# ProPrj_FireWheels_2025-05-02.net
KiCad netlist of a schematic drawn in EasyEDA Pro
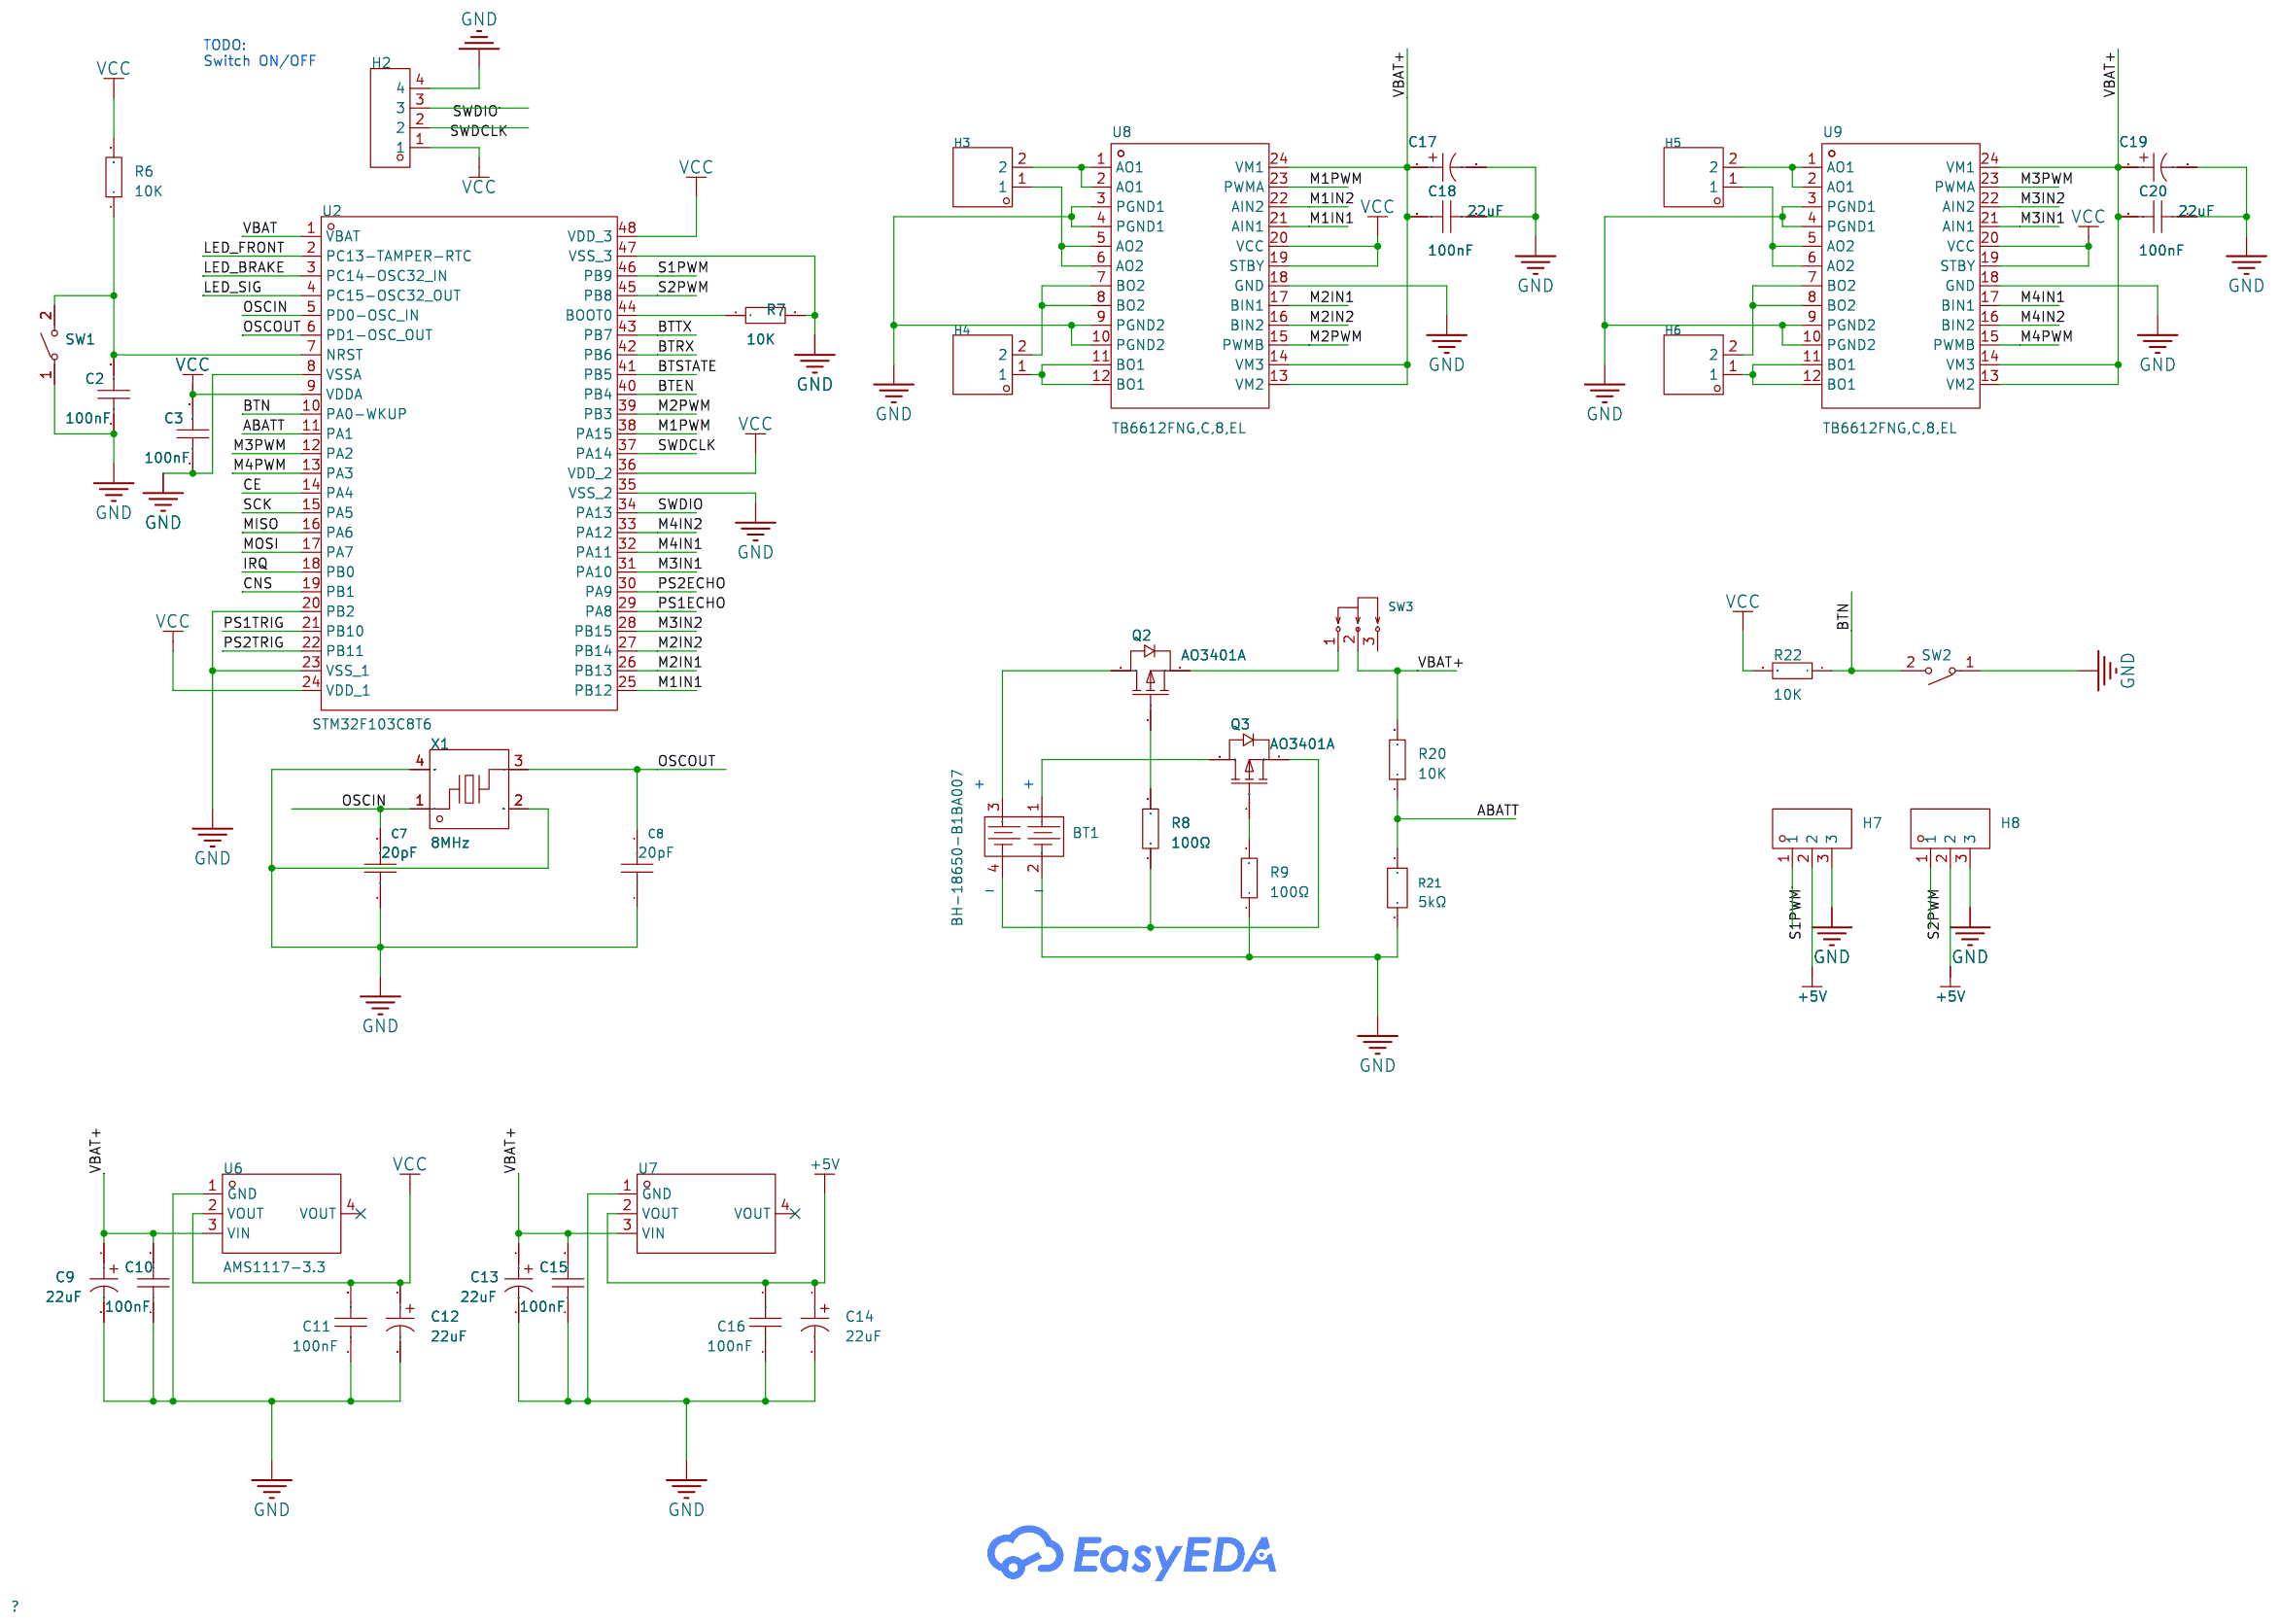
[diagram p0: P1]
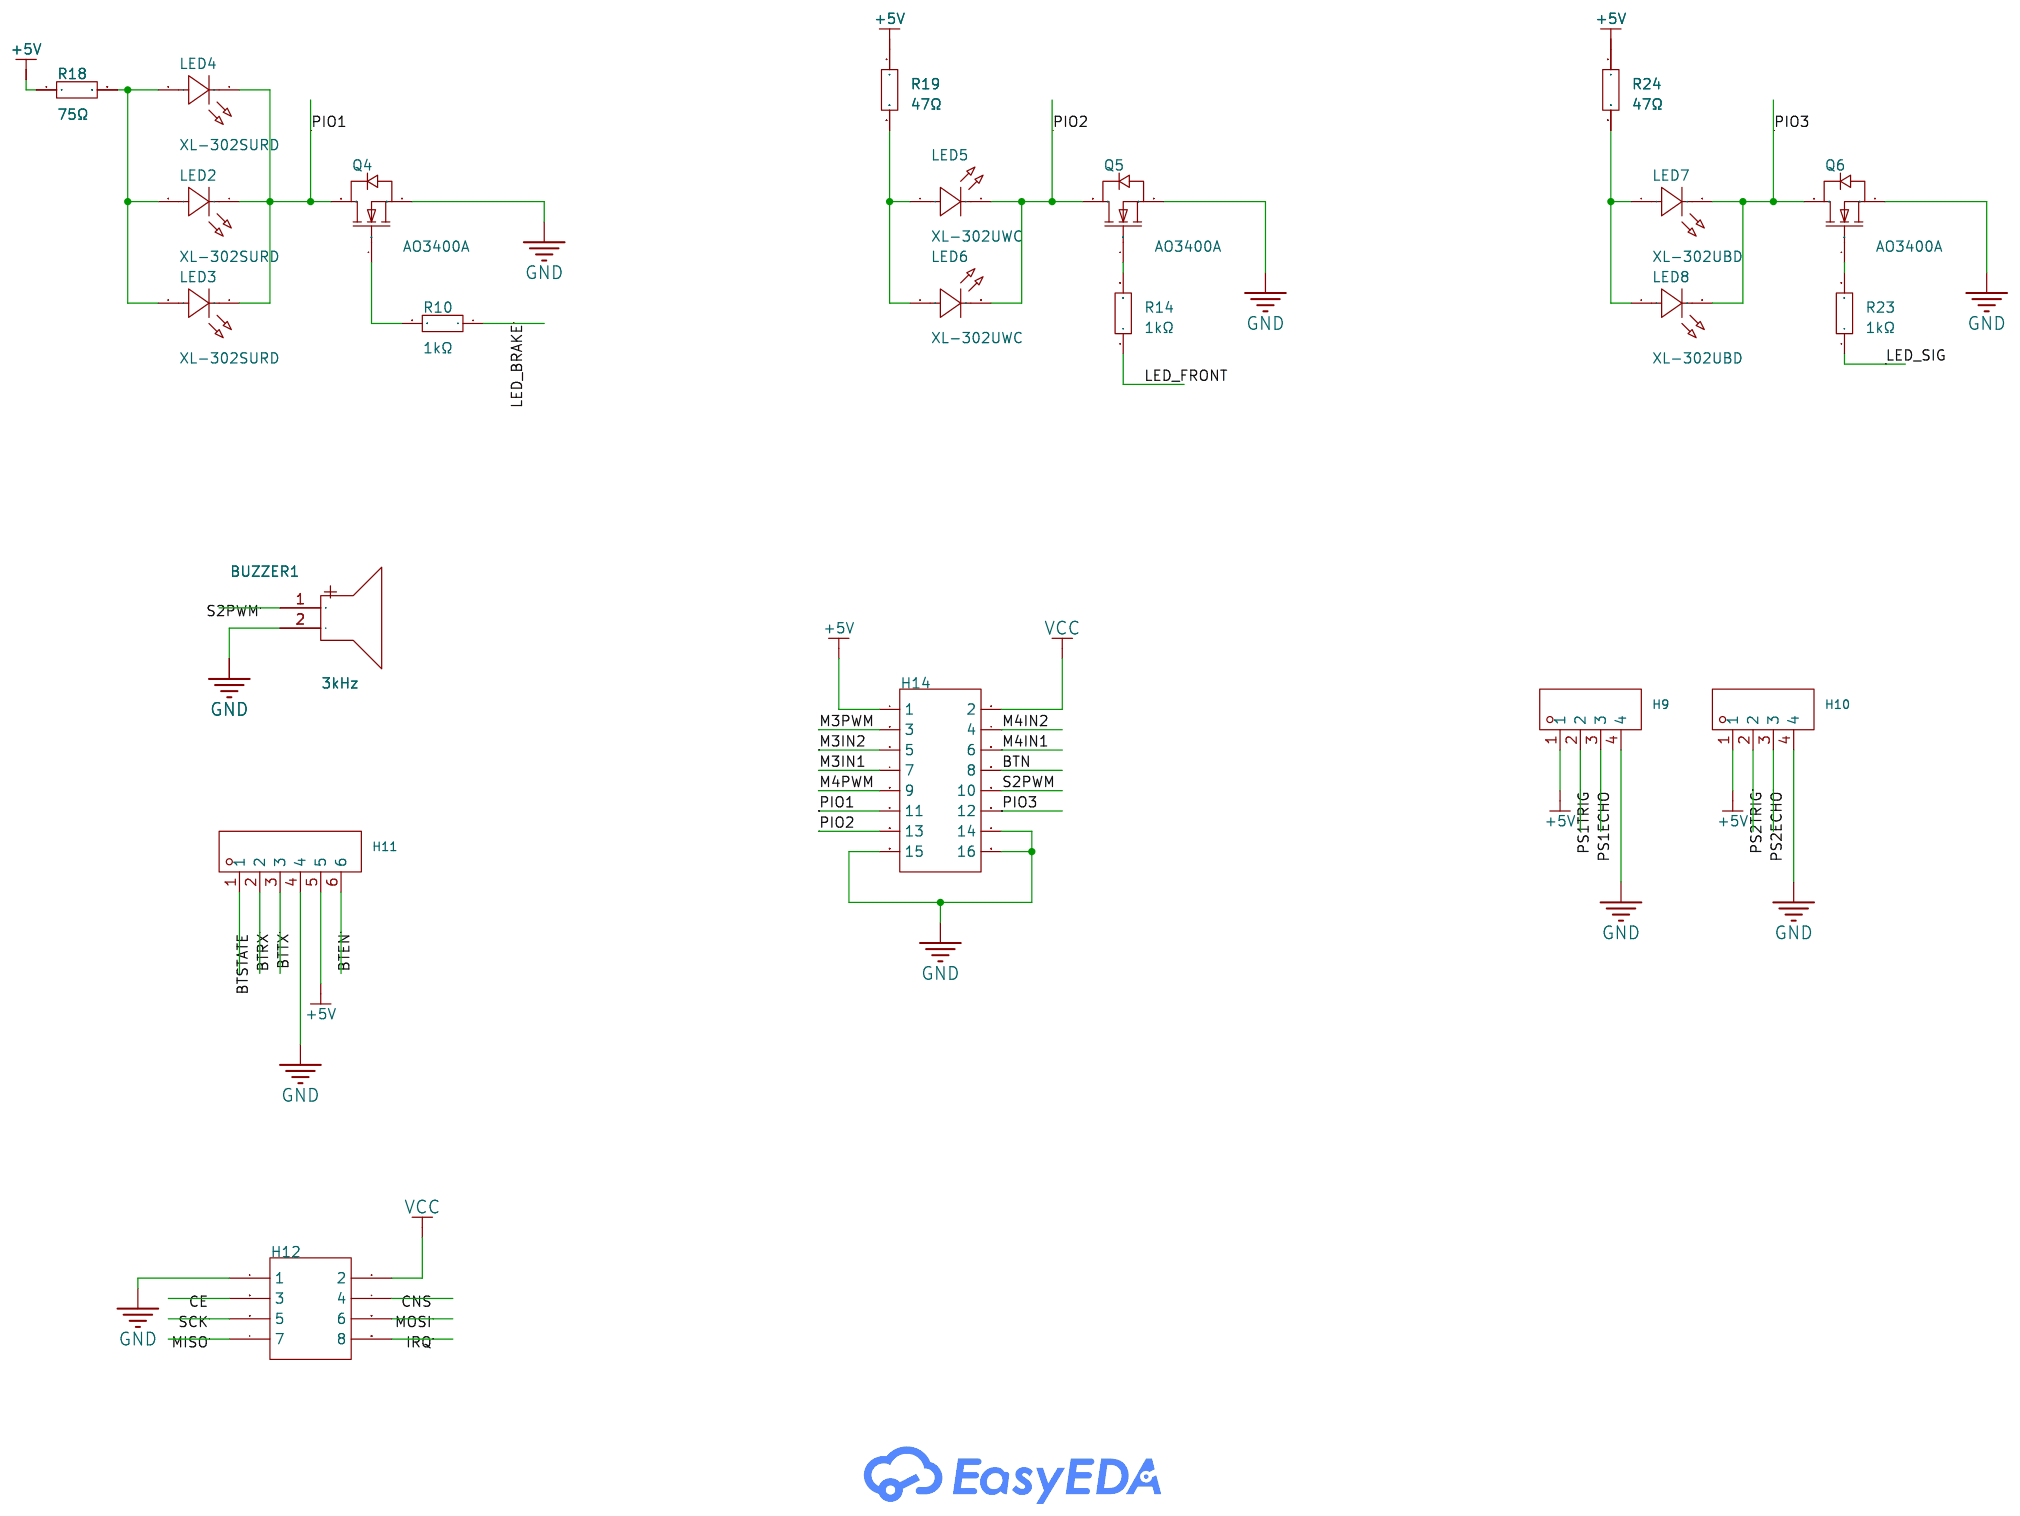
[diagram p1: P2]

(export (version "E")
  (design (tool "Eeschema 10.0.6"))
  (components
    (comp (ref "BT1")
      (value "BH-18650-B1BA007")
      (footprint "easyedapro:BAT-SMD_BH-18650-B1BA007")
      (fields (field (name "Manufacturer") "MYOUNG(美阳)"))
      (libsource (lib "easyedapro") (part "BH-18650-B1BA007"))
    )
    (comp (ref "C2")
      (value "100nF")
      (footprint "easyedapro:C0805")
      (fields (field (name "Manufacturer Part") "0805B104K250NT") (field (name "Manufacturer") "FH(风华)"))
      (libsource (lib "easyedapro") (part "0805B104K250NT"))
    )
    (comp (ref "C3")
      (value "100nF")
      (footprint "easyedapro:C0805")
      (fields (field (name "Manufacturer Part") "0805B104K250NT") (field (name "Manufacturer") "FH(风华)"))
      (libsource (lib "easyedapro") (part "0805B104K250NT"))
    )
    (comp (ref "C7")
      (value "20pF")
      (footprint "easyedapro:C0603")
      (fields
        (field (name "Manufacturer Part") "TCC0603COG200J500CT")
        (field (name "Manufacturer") "CCTC(三环)")
      )
      (libsource (lib "easyedapro") (part "TCC0603COG200J500CT"))
    )
    (comp (ref "C8")
      (value "20pF")
      (footprint "easyedapro:C0603")
      (fields
        (field (name "Manufacturer Part") "TCC0603COG200J500CT")
        (field (name "Manufacturer") "CCTC(三环)")
      )
      (libsource (lib "easyedapro") (part "TCC0603COG200J500CT"))
    )
    (comp (ref "C9")
      (value "22uF")
      (footprint "easyedapro:CAP-SMD_L3.5-W2.8-FD")
      (fields (field (name "Manufacturer Part") "T491B226K004AT") (field (name "Manufacturer") "KEMET(基美)"))
      (libsource (lib "easyedapro") (part "T491B226K004AT"))
    )
    (comp (ref "C10")
      (value "100nF")
      (footprint "easyedapro:C0805")
      (fields (field (name "Manufacturer Part") "0805B104K250NT") (field (name "Manufacturer") "FH(风华)"))
      (libsource (lib "easyedapro") (part "0805B104K250NT"))
    )
    (comp (ref "C11")
      (value "100nF")
      (footprint "easyedapro:C0805")
      (fields (field (name "Manufacturer Part") "0805B104K250NT") (field (name "Manufacturer") "FH(风华)"))
      (libsource (lib "easyedapro") (part "0805B104K250NT"))
    )
    (comp (ref "C12")
      (value "22uF")
      (footprint "easyedapro:CAP-SMD_L3.5-W2.8-FD")
      (fields (field (name "Manufacturer Part") "T491B226K004AT") (field (name "Manufacturer") "KEMET(基美)"))
      (libsource (lib "easyedapro") (part "T491B226K004AT"))
    )
    (comp (ref "C13")
      (value "22uF")
      (footprint "easyedapro:CAP-SMD_L3.5-W2.8-FD")
      (fields (field (name "Manufacturer Part") "T491B226K004AT") (field (name "Manufacturer") "KEMET(基美)"))
      (libsource (lib "easyedapro") (part "T491B226K004AT"))
    )
    (comp (ref "C14")
      (value "22uF")
      (footprint "easyedapro:CAP-SMD_L3.5-W2.8-FD")
      (fields (field (name "Manufacturer Part") "T491B226K004AT") (field (name "Manufacturer") "KEMET(基美)"))
      (libsource (lib "easyedapro") (part "T491B226K004AT"))
    )
    (comp (ref "C15")
      (value "100nF")
      (footprint "easyedapro:C0805")
      (fields (field (name "Manufacturer Part") "0805B104K250NT") (field (name "Manufacturer") "FH(风华)"))
      (libsource (lib "easyedapro") (part "0805B104K250NT"))
    )
    (comp (ref "C16")
      (value "100nF")
      (footprint "easyedapro:C0805")
      (fields (field (name "Manufacturer Part") "0805B104K250NT") (field (name "Manufacturer") "FH(风华)"))
      (libsource (lib "easyedapro") (part "0805B104K250NT"))
    )
    (comp (ref "C17")
      (value "22uF")
      (footprint "easyedapro:CAP-SMD_L3.5-W2.8-FD")
      (fields (field (name "Manufacturer Part") "T491B226K004AT") (field (name "Manufacturer") "KEMET(基美)"))
      (libsource (lib "easyedapro") (part "T491B226K004AT"))
    )
    (comp (ref "C18")
      (value "100nF")
      (footprint "easyedapro:C0805")
      (fields (field (name "Manufacturer Part") "0805B104K250NT") (field (name "Manufacturer") "FH(风华)"))
      (libsource (lib "easyedapro") (part "0805B104K250NT"))
    )
    (comp (ref "C19")
      (value "22uF")
      (footprint "easyedapro:CAP-SMD_L3.5-W2.8-FD")
      (fields (field (name "Manufacturer Part") "T491B226K004AT") (field (name "Manufacturer") "KEMET(基美)"))
      (libsource (lib "easyedapro") (part "T491B226K004AT"))
    )
    (comp (ref "C20")
      (value "100nF")
      (footprint "easyedapro:C0805")
      (fields (field (name "Manufacturer Part") "0805B104K250NT") (field (name "Manufacturer") "FH(风华)"))
      (libsource (lib "easyedapro") (part "0805B104K250NT"))
    )
    (comp (ref "H2")
      (value "~")
      (footprint "easyedapro:HDR-TH_4P-P2.54-V-M")
      (libsource (lib "easyedapro") (part "PZ254V-11-04P"))
    )
    (comp (ref "H3")
      (value "~")
      (footprint "easyedapro:HDR-TH_2P-P2.54-V-M-1")
      (libsource (lib "easyedapro") (part "210S-1*2P L=11.6MMGold-plated black"))
    )
    (comp (ref "H4")
      (value "~")
      (footprint "easyedapro:HDR-TH_2P-P2.54-V-M-1")
      (libsource (lib "easyedapro") (part "210S-1*2P L=11.6MMGold-plated black"))
    )
    (comp (ref "H5")
      (value "~")
      (footprint "easyedapro:HDR-TH_2P-P2.54-V-M-1")
      (libsource (lib "easyedapro") (part "210S-1*2P L=11.6MMGold-plated black"))
    )
    (comp (ref "H6")
      (value "~")
      (footprint "easyedapro:HDR-TH_2P-P2.54-V-M-1")
      (libsource (lib "easyedapro") (part "210S-1*2P L=11.6MMGold-plated black"))
    )
    (comp (ref "H7")
      (value "~")
      (footprint "easyedapro:HDR-TH_3P-P2.54-V-M")
      (libsource (lib "easyedapro") (part "PZ254V-11-03P_C2937625"))
    )
    (comp (ref "H8")
      (value "~")
      (footprint "easyedapro:HDR-TH_3P-P2.54-V-M")
      (libsource (lib "easyedapro") (part "PZ254V-11-03P_C2937625"))
    )
    (comp (ref "Q2")
      (value "AO3401A")
      (footprint "easyedapro:SOT-23_L2.9-W1.3-P1.90-LS2.4-BR")
      (fields (field (name "Manufacturer") "AOS"))
      (libsource (lib "easyedapro") (part "AO3401A"))
    )
    (comp (ref "Q3")
      (value "AO3401A")
      (footprint "easyedapro:SOT-23_L2.9-W1.3-P1.90-LS2.4-BR")
      (fields (field (name "Manufacturer") "AOS"))
      (libsource (lib "easyedapro") (part "AO3401A"))
    )
    (comp (ref "R6") (value "10K") (footprint "easyedapro:R0603") (libsource (lib "easyedapro") (part "Res")))
    (comp (ref "R7") (value "10K") (footprint "easyedapro:R0603") (libsource (lib "easyedapro") (part "Res")))
    (comp (ref "R8")
      (value "100Ω")
      (footprint "easyedapro:R0603")
      (fields
        (field (name "Manufacturer Part") "0603WAF1000T5E")
        (field (name "Manufacturer") "UNI-ROYAL(厚声)")
      )
      (libsource (lib "easyedapro") (part "0603WAF1000T5E"))
    )
    (comp (ref "R9")
      (value "100Ω")
      (footprint "easyedapro:R0603")
      (fields
        (field (name "Manufacturer Part") "0603WAF1000T5E")
        (field (name "Manufacturer") "UNI-ROYAL(厚声)")
      )
      (libsource (lib "easyedapro") (part "0603WAF1000T5E"))
    )
    (comp (ref "R20")
      (value "10K")
      (footprint "easyedapro:R0603")
      (libsource (lib "easyedapro") (part "Res"))
    )
    (comp (ref "R21")
      (value "5kΩ")
      (footprint "easyedapro:R0603")
      (fields (field (name "Manufacturer Part") "RTT035001FTP") (field (name "Manufacturer") "RALEC(旺诠)"))
      (libsource (lib "easyedapro") (part "RTT035001FTP"))
    )
    (comp (ref "R22")
      (value "10K")
      (footprint "easyedapro:R0603")
      (libsource (lib "easyedapro") (part "Res"))
    )
    (comp (ref "SW1")
      (value "~")
      (footprint "easyedapro:SW-SMD_L3.9-W3.0-P4.45")
      (fields (field (name "Manufacturer Part") "TS-1088R-02026") (field (name "Manufacturer") "XUNPU(讯普)"))
      (libsource (lib "easyedapro") (part "TS-1088R-02026"))
    )
    (comp (ref "SW2")
      (value "~")
      (footprint "easyedapro:SW-SMD_L3.9-W3.0-P4.45")
      (fields (field (name "Manufacturer Part") "TS-1088R-02026") (field (name "Manufacturer") "XUNPU(讯普)"))
      (libsource (lib "easyedapro") (part "TS-1088R-02026"))
    )
    (comp (ref "SW3")
      (value "SS12D10G4 071")
      (footprint "easyedapro:SW-TH_SHOU-HAN_SS12D10G4")
      (fields (field (name "Manufacturer") "SHOU HAN(首韩)"))
      (libsource (lib "easyedapro") (part "SS12D10G4 071"))
    )
    (comp (ref "U2")
      (value "STM32F103C8T6")
      (footprint "easyedapro:LQFP-48_L7.0-W7.0-P0.50-LS9.0-BL")
      (fields (field (name "Manufacturer") "ST(意法半导体)"))
      (libsource (lib "easyedapro") (part "STM32F103C8T6"))
    )
    (comp (ref "U6")
      (value "AMS1117-3.3")
      (footprint "easyedapro:SOT-223-3_L6.7-W3.7-P2.30-LS7.0-BR")
      (fields (field (name "Manufacturer") "JSMSEMI(杰盛微)"))
      (libsource (lib "easyedapro") (part "AMS1117-3.3_C917183"))
    )
    (comp (ref "U7")
      (value "~")
      (footprint "easyedapro:SOT-223_L6.5-W3.5-P2.30-LS7.0-BR")
      (fields (field (name "Manufacturer Part") "AMS1117-5.0") (field (name "Manufacturer") "美国AMS"))
      (libsource (lib "easyedapro") (part "AMS1117-5.0"))
    )
    (comp (ref "U8")
      (value "TB6612FNG,C,8,EL")
      (footprint "easyedapro:SSOP-24_L8.3-W5.6-P0.65-LS7.6-BL")
      (fields (field (name "Manufacturer") "TOSHIBA(东芝)"))
      (libsource (lib "easyedapro") (part "TB6612FNG,C,8,EL"))
    )
    (comp (ref "U9")
      (value "TB6612FNG,C,8,EL")
      (footprint "easyedapro:SSOP-24_L8.3-W5.6-P0.65-LS7.6-BL")
      (fields (field (name "Manufacturer") "TOSHIBA(东芝)"))
      (libsource (lib "easyedapro") (part "TB6612FNG,C,8,EL"))
    )
    (comp (ref "X1")
      (value "8MHz")
      (footprint "easyedapro:CRYSTAL-SMD_4P-L3.2-W2.5-BL")
      (fields (field (name "Manufacturer Part") "3TJ480000NWLAC") (field (name "Manufacturer") "JYJE(晶友嘉)"))
      (libsource (lib "easyedapro") (part "3TJ480000NWLAC"))
    )
    (comp (ref "BUZZER1")
      (value "3kHz")
      (footprint "easyedapro:BUZ-TH_BD9.0-P5.00-D0.6-FD")
      (fields (field (name "Manufacturer Part") "HNB09A03") (field (name "Manufacturer") "华能"))
      (libsource (lib "easyedapro") (part "HNB09A03"))
    )
    (comp (ref "H9")
      (value "~")
      (footprint "easyedapro:HDR-TH_4P-P2.54-V-F")
      (libsource (lib "easyedapro") (part "2.54-1*4P母"))
    )
    (comp (ref "H10")
      (value "~")
      (footprint "easyedapro:HDR-TH_4P-P2.54-V-F")
      (libsource (lib "easyedapro") (part "2.54-1*4P母"))
    )
    (comp (ref "H11")
      (value "~")
      (footprint "easyedapro:HDR-TH_6P-P2.54-V-F")
      (libsource (lib "easyedapro") (part "Header-Female-2.54_1x6"))
    )
    (comp (ref "H12")
      (value "~")
      (footprint "easyedapro:HDR-TH_8P-P2.54-V-F-R2-C4-S2.54-1")
      (libsource (lib "easyedapro") (part "HDR-F-2.54_2x4"))
    )
    (comp (ref "H14")
      (value "~")
      (footprint "easyedapro:HDR-TH_16P-P2.54-V-M-R2-C8-S2.54")
      (libsource (lib "easyedapro") (part "HDR-M-2.54_2x8"))
    )
    (comp (ref "LED2")
      (value "XL-302SURD")
      (footprint "easyedapro:LED-TH_BD3.8-P2.54-RD")
      (fields (field (name "Manufacturer") "XINGLIGHT(成兴光)"))
      (libsource (lib "easyedapro") (part "XL-302SURD"))
    )
    (comp (ref "LED3")
      (value "XL-302SURD")
      (footprint "easyedapro:LED-TH_BD3.8-P2.54-RD")
      (fields (field (name "Manufacturer") "XINGLIGHT(成兴光)"))
      (libsource (lib "easyedapro") (part "XL-302SURD"))
    )
    (comp (ref "LED4")
      (value "XL-302SURD")
      (footprint "easyedapro:LED-TH_BD3.8-P2.54-RD")
      (fields (field (name "Manufacturer") "XINGLIGHT(成兴光)"))
      (libsource (lib "easyedapro") (part "XL-302SURD"))
    )
    (comp (ref "LED5")
      (value "XL-302UWC")
      (footprint "easyedapro:LED-TH_BD3.8-P2.54-FD_WHITE")
      (fields (field (name "Manufacturer") "XINGLIGHT(成兴光)"))
      (libsource (lib "easyedapro") (part "XL-302UWC"))
    )
    (comp (ref "LED6")
      (value "XL-302UWC")
      (footprint "easyedapro:LED-TH_BD3.8-P2.54-FD_WHITE")
      (fields (field (name "Manufacturer") "XINGLIGHT(成兴光)"))
      (libsource (lib "easyedapro") (part "XL-302UWC"))
    )
    (comp (ref "LED7")
      (value "XL-302UBD")
      (footprint "easyedapro:LED-TH_BD3.8-P2.54-FD_BLUE")
      (fields (field (name "Manufacturer") "XINGLIGHT(成兴光)"))
      (libsource (lib "easyedapro") (part "XL-302UBD"))
    )
    (comp (ref "LED8")
      (value "XL-302UBD")
      (footprint "easyedapro:LED-TH_BD3.8-P2.54-FD_BLUE")
      (fields (field (name "Manufacturer") "XINGLIGHT(成兴光)"))
      (libsource (lib "easyedapro") (part "XL-302UBD"))
    )
    (comp (ref "Q4")
      (value "AO3400A")
      (footprint "easyedapro:SOT-23-3_L2.9-W1.3-P1.90-LS2.4-BR")
      (fields (field (name "Manufacturer") "AOS"))
      (libsource (lib "easyedapro") (part "AO3400A"))
    )
    (comp (ref "Q5")
      (value "AO3400A")
      (footprint "easyedapro:SOT-23-3_L2.9-W1.3-P1.90-LS2.4-BR")
      (fields (field (name "Manufacturer") "AOS"))
      (libsource (lib "easyedapro") (part "AO3400A"))
    )
    (comp (ref "Q6")
      (value "AO3400A")
      (footprint "easyedapro:SOT-23-3_L2.9-W1.3-P1.90-LS2.4-BR")
      (fields (field (name "Manufacturer") "AOS"))
      (libsource (lib "easyedapro") (part "AO3400A"))
    )
    (comp (ref "R10")
      (value "1kΩ")
      (footprint "easyedapro:R0603")
      (fields (field (name "Manufacturer Part") "RC0603FR-071KL") (field (name "Manufacturer") "YAGEO(国巨)"))
      (libsource (lib "easyedapro") (part "RC0603FR-071KL"))
    )
    (comp (ref "R14")
      (value "1kΩ")
      (footprint "easyedapro:R0603")
      (fields (field (name "Manufacturer Part") "RC0603FR-071KL") (field (name "Manufacturer") "YAGEO(国巨)"))
      (libsource (lib "easyedapro") (part "RC0603FR-071KL"))
    )
    (comp (ref "R18")
      (value "75Ω")
      (footprint "easyedapro:R1206")
      (fields (field (name "Manufacturer Part") "RC1206FR-0775RL") (field (name "Manufacturer") "YAGEO(国巨)"))
      (libsource (lib "easyedapro") (part "RC1206FR-0775RL"))
    )
    (comp (ref "R19")
      (value "47Ω")
      (footprint "easyedapro:R1206")
      (fields (field (name "Manufacturer Part") "RC1206FR-0747RL") (field (name "Manufacturer") "YAGEO(国巨)"))
      (libsource (lib "easyedapro") (part "RC1206FR-0747RL"))
    )
    (comp (ref "R23")
      (value "1kΩ")
      (footprint "easyedapro:R0603")
      (fields (field (name "Manufacturer Part") "RC0603FR-071KL") (field (name "Manufacturer") "YAGEO(国巨)"))
      (libsource (lib "easyedapro") (part "RC0603FR-071KL"))
    )
    (comp (ref "R24")
      (value "47Ω")
      (footprint "easyedapro:R1206")
      (fields (field (name "Manufacturer Part") "RC1206FR-0747RL") (field (name "Manufacturer") "YAGEO(国巨)"))
      (libsource (lib "easyedapro") (part "RC1206FR-0747RL"))
    )
  )
  (nets
    (net (code "1") (name "+5V") (class "Default")
      (node (ref "C14") (pin "1") (pinfunction "1_1") (pintype "input"))
      (node (ref "C16") (pin "2") (pinfunction "2_2") (pintype "unspecified"))
      (node (ref "H10") (pin "1") (pinfunction "1_1") (pintype "input"))
      (node (ref "H11") (pin "5") (pinfunction "5_5") (pintype "input"))
      (node (ref "H14") (pin "1") (pinfunction "1_1") (pintype "input"))
      (node (ref "H7") (pin "2") (pinfunction "2_2") (pintype "unspecified"))
      (node (ref "H8") (pin "2") (pinfunction "2_2") (pintype "unspecified"))
      (node (ref "H9") (pin "1") (pinfunction "1_1") (pintype "input"))
      (node (ref "R18") (pin "1") (pinfunction "1_1") (pintype "input"))
      (node (ref "R19") (pin "1") (pinfunction "1_1") (pintype "input"))
      (node (ref "R24") (pin "1") (pinfunction "1_1") (pintype "input"))
      (node (ref "U7") (pin "2") (pinfunction "VOUT_2") (pintype "input"))
    )
    (net (code "2") (name "ABATT") (class "Default")
      (node (ref "R20") (pin "1") (pinfunction "1_1") (pintype "input"))
      (node (ref "R21") (pin "2") (pinfunction "2_2") (pintype "input"))
      (node (ref "U2") (pin "11") (pinfunction "PA1_11") (pintype "unspecified"))
    )
    (net (code "3") (name "BTEN") (class "Default")
      (node (ref "H11") (pin "6") (pinfunction "6_6") (pintype "input"))
      (node (ref "U2") (pin "40") (pinfunction "PB4_40") (pintype "unspecified"))
    )
    (net (code "4") (name "BTN") (class "Default")
      (node (ref "H14") (pin "8") (pinfunction "8_8") (pintype "input"))
      (node (ref "R22") (pin "1") (pinfunction "1_1") (pintype "input"))
      (node (ref "SW2") (pin "2") (pinfunction "2_2") (pintype "input"))
      (node (ref "U2") (pin "10") (pinfunction "PA0-WKUP_10") (pintype "unspecified"))
    )
    (net (code "5") (name "BTRX") (class "Default")
      (node (ref "H11") (pin "2") (pinfunction "2_2") (pintype "input"))
      (node (ref "U2") (pin "42") (pinfunction "PB6_42") (pintype "unspecified"))
    )
    (net (code "6") (name "BTSTATE") (class "Default")
      (node (ref "H11") (pin "1") (pinfunction "1_1") (pintype "input"))
      (node (ref "U2") (pin "41") (pinfunction "PB5_41") (pintype "unspecified"))
    )
    (net (code "7") (name "BTTX") (class "Default")
      (node (ref "H11") (pin "3") (pinfunction "3_3") (pintype "input"))
      (node (ref "U2") (pin "43") (pinfunction "PB7_43") (pintype "unspecified"))
    )
    (net (code "8") (name "CE") (class "Default")
      (node (ref "H12") (pin "3") (pinfunction "3_3") (pintype "input"))
      (node (ref "U2") (pin "14") (pinfunction "PA4_14") (pintype "unspecified"))
    )
    (net (code "9") (name "CNS") (class "Default")
      (node (ref "H12") (pin "4") (pinfunction "4_4") (pintype "input"))
      (node (ref "U2") (pin "19") (pinfunction "PB1_19") (pintype "unspecified"))
    )
    (net (code "10") (name "GND") (class "Default")
      (node (ref "BT1") (pin "2") (pinfunction "2_2") (pintype "input"))
      (node (ref "BUZZER1") (pin "2") (pinfunction "-_2") (pintype "unspecified"))
      (node (ref "C10") (pin "1") (pinfunction "1_1") (pintype "unspecified"))
      (node (ref "C11") (pin "1") (pinfunction "1_1") (pintype "unspecified"))
      (node (ref "C12") (pin "2") (pinfunction "2_2") (pintype "input"))
      (node (ref "C13") (pin "2") (pinfunction "2_2") (pintype "input"))
      (node (ref "C14") (pin "2") (pinfunction "2_2") (pintype "input"))
      (node (ref "C15") (pin "1") (pinfunction "1_1") (pintype "unspecified"))
      (node (ref "C16") (pin "1") (pinfunction "1_1") (pintype "unspecified"))
      (node (ref "C17") (pin "2") (pinfunction "2_2") (pintype "input"))
      (node (ref "C18") (pin "1") (pinfunction "1_1") (pintype "unspecified"))
      (node (ref "C19") (pin "2") (pinfunction "2_2") (pintype "input"))
      (node (ref "C2") (pin "1") (pinfunction "1_1") (pintype "unspecified"))
      (node (ref "C20") (pin "1") (pinfunction "1_1") (pintype "unspecified"))
      (node (ref "C3") (pin "1") (pinfunction "1_1") (pintype "unspecified"))
      (node (ref "C7") (pin "1") (pinfunction "1_1") (pintype "input"))
      (node (ref "C8") (pin "1") (pinfunction "1_1") (pintype "input"))
      (node (ref "C9") (pin "2") (pinfunction "2_2") (pintype "input"))
      (node (ref "H10") (pin "4") (pinfunction "4_4") (pintype "input"))
      (node (ref "H11") (pin "4") (pinfunction "4_4") (pintype "input"))
      (node (ref "H12") (pin "1") (pinfunction "1_1") (pintype "input"))
      (node (ref "H14") (pin "14") (pinfunction "14_14") (pintype "input"))
      (node (ref "H14") (pin "15") (pinfunction "15_15") (pintype "input"))
      (node (ref "H14") (pin "16") (pinfunction "16_16") (pintype "input"))
      (node (ref "H2") (pin "4") (pinfunction "4_4") (pintype "unspecified"))
      (node (ref "H7") (pin "3") (pinfunction "3_3") (pintype "unspecified"))
      (node (ref "H8") (pin "3") (pinfunction "3_3") (pintype "unspecified"))
      (node (ref "H9") (pin "4") (pinfunction "4_4") (pintype "input"))
      (node (ref "Q4") (pin "2") (pinfunction "S_2") (pintype "unspecified"))
      (node (ref "Q5") (pin "2") (pinfunction "S_2") (pintype "unspecified"))
      (node (ref "Q6") (pin "2") (pinfunction "S_2") (pintype "unspecified"))
      (node (ref "R21") (pin "1") (pinfunction "1_1") (pintype "input"))
      (node (ref "R7") (pin "2") (pinfunction "2_2") (pintype "input"))
      (node (ref "R9") (pin "1") (pinfunction "1_1") (pintype "input"))
      (node (ref "SW1") (pin "1") (pinfunction "1_1") (pintype "input"))
      (node (ref "SW2") (pin "1") (pinfunction "1_1") (pintype "input"))
      (node (ref "U2") (pin "20") (pinfunction "PB2_20") (pintype "unspecified"))
      (node (ref "U2") (pin "23") (pinfunction "VSS_1_23") (pintype "unspecified"))
      (node (ref "U2") (pin "35") (pinfunction "VSS_2_35") (pintype "unspecified"))
      (node (ref "U2") (pin "47") (pinfunction "VSS_3_47") (pintype "unspecified"))
      (node (ref "U2") (pin "8") (pinfunction "VSSA_8") (pintype "unspecified"))
      (node (ref "U6") (pin "1") (pinfunction "GND_1") (pintype "unspecified"))
      (node (ref "U7") (pin "1") (pinfunction "GND_1") (pintype "input"))
      (node (ref "U8") (pin "10") (pinfunction "PGND2_10") (pintype "unspecified"))
      (node (ref "U8") (pin "18") (pinfunction "GND_18") (pintype "unspecified"))
      (node (ref "U8") (pin "3") (pinfunction "PGND1_3") (pintype "unspecified"))
      (node (ref "U8") (pin "4") (pinfunction "PGND1_4") (pintype "unspecified"))
      (node (ref "U8") (pin "9") (pinfunction "PGND2_9") (pintype "unspecified"))
      (node (ref "U9") (pin "10") (pinfunction "PGND2_10") (pintype "unspecified"))
      (node (ref "U9") (pin "18") (pinfunction "GND_18") (pintype "unspecified"))
      (node (ref "U9") (pin "3") (pinfunction "PGND1_3") (pintype "unspecified"))
      (node (ref "U9") (pin "4") (pinfunction "PGND1_4") (pintype "unspecified"))
      (node (ref "U9") (pin "9") (pinfunction "PGND2_9") (pintype "unspecified"))
      (node (ref "X1") (pin "2") (pinfunction "GND_2") (pintype "input"))
      (node (ref "X1") (pin "4") (pinfunction "GND_4") (pintype "input"))
    )
    (net (code "11") (name "IRQ") (class "Default")
      (node (ref "H12") (pin "8") (pinfunction "8_8") (pintype "input"))
      (node (ref "U2") (pin "18") (pinfunction "PB0_18") (pintype "unspecified"))
    )
    (net (code "12") (name "LED_BRAKE") (class "Default")
      (node (ref "R10") (pin "1") (pinfunction "1_1") (pintype "input"))
      (node (ref "U2") (pin "3") (pinfunction "PC14-OSC32_IN_3") (pintype "unspecified"))
    )
    (net (code "13") (name "LED_FRONT") (class "Default")
      (node (ref "R14") (pin "1") (pinfunction "1_1") (pintype "input"))
      (node (ref "U2") (pin "2") (pinfunction "PC13-TAMPER-RTC_2") (pintype "unspecified"))
    )
    (net (code "14") (name "LED_SIG") (class "Default")
      (node (ref "R23") (pin "1") (pinfunction "1_1") (pintype "input"))
      (node (ref "U2") (pin "4") (pinfunction "PC15-OSC32_OUT_4") (pintype "unspecified"))
    )
    (net (code "15") (name "M1IN1") (class "Default")
      (node (ref "U2") (pin "25") (pinfunction "PB12_25") (pintype "unspecified"))
      (node (ref "U8") (pin "21") (pinfunction "AIN1_21") (pintype "unspecified"))
    )
    (net (code "16") (name "M1IN2") (class "Default")
      (node (ref "U8") (pin "22") (pinfunction "AIN2_22") (pintype "unspecified"))
    )
    (net (code "17") (name "M1PWM") (class "Default")
      (node (ref "U2") (pin "38") (pinfunction "PA15_38") (pintype "unspecified"))
      (node (ref "U8") (pin "23") (pinfunction "PWMA_23") (pintype "unspecified"))
    )
    (net (code "18") (name "M2IN1") (class "Default")
      (node (ref "U2") (pin "26") (pinfunction "PB13_26") (pintype "unspecified"))
      (node (ref "U8") (pin "17") (pinfunction "BIN1_17") (pintype "unspecified"))
    )
    (net (code "19") (name "M2IN2") (class "Default")
      (node (ref "U2") (pin "27") (pinfunction "PB14_27") (pintype "unspecified"))
      (node (ref "U8") (pin "16") (pinfunction "BIN2_16") (pintype "unspecified"))
    )
    (net (code "20") (name "M2PWM") (class "Default")
      (node (ref "U2") (pin "39") (pinfunction "PB3_39") (pintype "unspecified"))
      (node (ref "U8") (pin "15") (pinfunction "PWMB_15") (pintype "unspecified"))
    )
    (net (code "21") (name "M3IN1") (class "Default")
      (node (ref "H14") (pin "7") (pinfunction "7_7") (pintype "input"))
      (node (ref "U2") (pin "31") (pinfunction "PA10_31") (pintype "unspecified"))
      (node (ref "U9") (pin "21") (pinfunction "AIN1_21") (pintype "unspecified"))
    )
    (net (code "22") (name "M3IN2") (class "Default")
      (node (ref "H14") (pin "5") (pinfunction "5_5") (pintype "input"))
      (node (ref "U2") (pin "28") (pinfunction "PB15_28") (pintype "unspecified"))
      (node (ref "U9") (pin "22") (pinfunction "AIN2_22") (pintype "unspecified"))
    )
    (net (code "23") (name "M3PWM") (class "Default")
      (node (ref "H14") (pin "3") (pinfunction "3_3") (pintype "input"))
      (node (ref "U2") (pin "12") (pinfunction "PA2_12") (pintype "unspecified"))
      (node (ref "U9") (pin "23") (pinfunction "PWMA_23") (pintype "unspecified"))
    )
    (net (code "24") (name "M4IN1") (class "Default")
      (node (ref "H14") (pin "6") (pinfunction "6_6") (pintype "input"))
      (node (ref "U2") (pin "32") (pinfunction "PA11_32") (pintype "unspecified"))
      (node (ref "U9") (pin "17") (pinfunction "BIN1_17") (pintype "unspecified"))
    )
    (net (code "25") (name "M4IN2") (class "Default")
      (node (ref "H14") (pin "4") (pinfunction "4_4") (pintype "input"))
      (node (ref "U2") (pin "33") (pinfunction "PA12_33") (pintype "unspecified"))
      (node (ref "U9") (pin "16") (pinfunction "BIN2_16") (pintype "unspecified"))
    )
    (net (code "26") (name "M4PWM") (class "Default")
      (node (ref "H14") (pin "9") (pinfunction "9_9") (pintype "input"))
      (node (ref "U2") (pin "13") (pinfunction "PA3_13") (pintype "unspecified"))
      (node (ref "U9") (pin "15") (pinfunction "PWMB_15") (pintype "unspecified"))
    )
    (net (code "27") (name "MISO") (class "Default")
      (node (ref "H12") (pin "7") (pinfunction "7_7") (pintype "input"))
      (node (ref "U2") (pin "16") (pinfunction "PA6_16") (pintype "unspecified"))
    )
    (net (code "28") (name "MOSI") (class "Default")
      (node (ref "H12") (pin "6") (pinfunction "6_6") (pintype "input"))
      (node (ref "U2") (pin "17") (pinfunction "PA7_17") (pintype "unspecified"))
    )
    (net (code "29") (name "Net-(H3-Pad1)") (class "Default")
      (node (ref "H3") (pin "1") (pinfunction "1_1") (pintype "input"))
      (node (ref "U8") (pin "5") (pinfunction "AO2_5") (pintype "unspecified"))
      (node (ref "U8") (pin "6") (pinfunction "AO2_6") (pintype "unspecified"))
    )
    (net (code "30") (name "Net-(H3-Pad2)") (class "Default")
      (node (ref "H3") (pin "2") (pinfunction "2_2") (pintype "input"))
      (node (ref "U8") (pin "1") (pinfunction "AO1_1") (pintype "unspecified"))
      (node (ref "U8") (pin "2") (pinfunction "AO1_2") (pintype "unspecified"))
    )
    (net (code "31") (name "Net-(H4-Pad1)") (class "Default")
      (node (ref "H4") (pin "1") (pinfunction "1_1") (pintype "input"))
      (node (ref "U8") (pin "11") (pinfunction "BO1_11") (pintype "unspecified"))
      (node (ref "U8") (pin "12") (pinfunction "BO1_12") (pintype "unspecified"))
    )
    (net (code "32") (name "Net-(H4-Pad2)") (class "Default")
      (node (ref "H4") (pin "2") (pinfunction "2_2") (pintype "input"))
      (node (ref "U8") (pin "7") (pinfunction "BO2_7") (pintype "unspecified"))
      (node (ref "U8") (pin "8") (pinfunction "BO2_8") (pintype "unspecified"))
    )
    (net (code "33") (name "Net-(H5-Pad1)") (class "Default")
      (node (ref "H5") (pin "1") (pinfunction "1_1") (pintype "input"))
      (node (ref "U9") (pin "5") (pinfunction "AO2_5") (pintype "unspecified"))
      (node (ref "U9") (pin "6") (pinfunction "AO2_6") (pintype "unspecified"))
    )
    (net (code "34") (name "Net-(H5-Pad2)") (class "Default")
      (node (ref "H5") (pin "2") (pinfunction "2_2") (pintype "input"))
      (node (ref "U9") (pin "1") (pinfunction "AO1_1") (pintype "unspecified"))
      (node (ref "U9") (pin "2") (pinfunction "AO1_2") (pintype "unspecified"))
    )
    (net (code "35") (name "Net-(H6-Pad1)") (class "Default")
      (node (ref "H6") (pin "1") (pinfunction "1_1") (pintype "input"))
      (node (ref "U9") (pin "11") (pinfunction "BO1_11") (pintype "unspecified"))
      (node (ref "U9") (pin "12") (pinfunction "BO1_12") (pintype "unspecified"))
    )
    (net (code "36") (name "Net-(H6-Pad2)") (class "Default")
      (node (ref "H6") (pin "2") (pinfunction "2_2") (pintype "input"))
      (node (ref "U9") (pin "7") (pinfunction "BO2_7") (pintype "unspecified"))
      (node (ref "U9") (pin "8") (pinfunction "BO2_8") (pintype "unspecified"))
    )
    (net (code "37") (name "Net-(LED2-A)") (class "Default")
      (node (ref "LED2") (pin "2") (pinfunction "A_2") (pintype "unspecified"))
      (node (ref "LED3") (pin "2") (pinfunction "A_2") (pintype "unspecified"))
      (node (ref "LED4") (pin "2") (pinfunction "A_2") (pintype "unspecified"))
      (node (ref "R18") (pin "2") (pinfunction "2_2") (pintype "input"))
    )
    (net (code "38") (name "Net-(LED5-A)") (class "Default")
      (node (ref "LED5") (pin "1") (pinfunction "A_1") (pintype "unspecified"))
      (node (ref "LED6") (pin "1") (pinfunction "A_1") (pintype "unspecified"))
      (node (ref "R19") (pin "2") (pinfunction "2_2") (pintype "input"))
    )
    (net (code "39") (name "Net-(LED7-K)") (class "Default")
      (node (ref "LED7") (pin "1") (pinfunction "K_1") (pintype "unspecified"))
      (node (ref "LED8") (pin "1") (pinfunction "K_1") (pintype "unspecified"))
      (node (ref "R24") (pin "2") (pinfunction "2_2") (pintype "input"))
    )
    (net (code "40") (name "Net-(Q2-D)") (class "Default")
      (node (ref "BT1") (pin "3") (pinfunction "3_3") (pintype "input"))
      (node (ref "Q2") (pin "3") (pinfunction "D_3") (pintype "unspecified"))
    )
    (net (code "41") (name "Net-(Q2-G)") (class "Default")
      (node (ref "Q2") (pin "1") (pinfunction "G_1") (pintype "unspecified"))
      (node (ref "R8") (pin "2") (pinfunction "2_2") (pintype "input"))
    )
    (net (code "42") (name "Net-(Q2-S)") (class "Default")
      (node (ref "Q2") (pin "2") (pinfunction "S_2") (pintype "unspecified"))
      (node (ref "SW3") (pin "1") (pinfunction "1_1") (pintype "input"))
    )
    (net (code "43") (name "Net-(Q3-D)") (class "Default")
      (node (ref "BT1") (pin "1") (pinfunction "1_1") (pintype "input"))
      (node (ref "Q3") (pin "3") (pinfunction "D_3") (pintype "unspecified"))
    )
    (net (code "44") (name "Net-(Q3-G)") (class "Default")
      (node (ref "Q3") (pin "1") (pinfunction "G_1") (pintype "unspecified"))
      (node (ref "R9") (pin "2") (pinfunction "2_2") (pintype "input"))
    )
    (net (code "45") (name "Net-(Q3-S)") (class "Default")
      (node (ref "BT1") (pin "4") (pinfunction "4_4") (pintype "input"))
      (node (ref "Q3") (pin "2") (pinfunction "S_2") (pintype "unspecified"))
      (node (ref "R8") (pin "1") (pinfunction "1_1") (pintype "input"))
    )
    (net (code "46") (name "Net-(Q4-G)") (class "Default")
      (node (ref "Q4") (pin "1") (pinfunction "G_1") (pintype "unspecified"))
      (node (ref "R10") (pin "2") (pinfunction "2_2") (pintype "input"))
    )
    (net (code "47") (name "Net-(Q5-G)") (class "Default")
      (node (ref "Q5") (pin "1") (pinfunction "G_1") (pintype "unspecified"))
      (node (ref "R14") (pin "2") (pinfunction "2_2") (pintype "input"))
    )
    (net (code "48") (name "Net-(Q6-G)") (class "Default")
      (node (ref "Q6") (pin "1") (pinfunction "G_1") (pintype "unspecified"))
      (node (ref "R23") (pin "2") (pinfunction "2_2") (pintype "input"))
    )
    (net (code "49") (name "Net-(U2-BOOT0)") (class "Default")
      (node (ref "R7") (pin "1") (pinfunction "1_1") (pintype "input"))
      (node (ref "U2") (pin "44") (pinfunction "BOOT0_44") (pintype "unspecified"))
    )
    (net (code "50") (name "Net-(U2-NRST)") (class "Default")
      (node (ref "C2") (pin "2") (pinfunction "2_2") (pintype "unspecified"))
      (node (ref "R6") (pin "1") (pinfunction "1_1") (pintype "input"))
      (node (ref "SW1") (pin "2") (pinfunction "2_2") (pintype "input"))
      (node (ref "U2") (pin "7") (pinfunction "NRST_7") (pintype "unspecified"))
    )
    (net (code "51") (name "OSCIN") (class "Default")
      (node (ref "C7") (pin "2") (pinfunction "2_2") (pintype "input"))
      (node (ref "U2") (pin "5") (pinfunction "PD0-OSC_IN_5") (pintype "unspecified"))
      (node (ref "X1") (pin "1") (pinfunction "1_1") (pintype "input"))
    )
    (net (code "52") (name "OSCOUT") (class "Default")
      (node (ref "C8") (pin "2") (pinfunction "2_2") (pintype "input"))
      (node (ref "U2") (pin "6") (pinfunction "PD1-OSC_OUT_6") (pintype "unspecified"))
      (node (ref "X1") (pin "3") (pinfunction "3_3") (pintype "input"))
    )
    (net (code "53") (name "PIO1") (class "Default")
      (node (ref "H14") (pin "11") (pinfunction "11_11") (pintype "input"))
      (node (ref "LED2") (pin "1") (pinfunction "K_1") (pintype "unspecified"))
      (node (ref "LED3") (pin "1") (pinfunction "K_1") (pintype "unspecified"))
      (node (ref "LED4") (pin "1") (pinfunction "K_1") (pintype "unspecified"))
      (node (ref "Q4") (pin "3") (pinfunction "D_3") (pintype "unspecified"))
    )
    (net (code "54") (name "PIO2") (class "Default")
      (node (ref "H14") (pin "13") (pinfunction "13_13") (pintype "input"))
      (node (ref "LED5") (pin "2") (pinfunction "K_2") (pintype "unspecified"))
      (node (ref "LED6") (pin "2") (pinfunction "K_2") (pintype "unspecified"))
      (node (ref "Q5") (pin "3") (pinfunction "D_3") (pintype "unspecified"))
    )
    (net (code "55") (name "PIO3") (class "Default")
      (node (ref "H14") (pin "12") (pinfunction "12_12") (pintype "input"))
      (node (ref "LED7") (pin "2") (pinfunction "A_2") (pintype "unspecified"))
      (node (ref "LED8") (pin "2") (pinfunction "A_2") (pintype "unspecified"))
      (node (ref "Q6") (pin "3") (pinfunction "D_3") (pintype "unspecified"))
    )
    (net (code "56") (name "PS1ECHO") (class "Default")
      (node (ref "H9") (pin "3") (pinfunction "3_3") (pintype "input"))
      (node (ref "U2") (pin "29") (pinfunction "PA8_29") (pintype "unspecified"))
    )
    (net (code "57") (name "PS1TRIG") (class "Default")
      (node (ref "H9") (pin "2") (pinfunction "2_2") (pintype "input"))
      (node (ref "U2") (pin "21") (pinfunction "PB10_21") (pintype "unspecified"))
    )
    (net (code "58") (name "PS2ECHO") (class "Default")
      (node (ref "H10") (pin "3") (pinfunction "3_3") (pintype "input"))
      (node (ref "U2") (pin "30") (pinfunction "PA9_30") (pintype "unspecified"))
    )
    (net (code "59") (name "PS2TRIG") (class "Default")
      (node (ref "H10") (pin "2") (pinfunction "2_2") (pintype "input"))
      (node (ref "U2") (pin "22") (pinfunction "PB11_22") (pintype "unspecified"))
    )
    (net (code "60") (name "S1PWM") (class "Default")
      (node (ref "H7") (pin "1") (pinfunction "1_1") (pintype "unspecified"))
      (node (ref "U2") (pin "46") (pinfunction "PB9_46") (pintype "unspecified"))
    )
    (net (code "61") (name "S2PWM") (class "Default")
      (node (ref "BUZZER1") (pin "1") (pinfunction "+_1") (pintype "unspecified"))
      (node (ref "H14") (pin "10") (pinfunction "10_10") (pintype "input"))
      (node (ref "H8") (pin "1") (pinfunction "1_1") (pintype "unspecified"))
      (node (ref "U2") (pin "45") (pinfunction "PB8_45") (pintype "unspecified"))
    )
    (net (code "62") (name "SCK") (class "Default")
      (node (ref "H12") (pin "5") (pinfunction "5_5") (pintype "input"))
      (node (ref "U2") (pin "15") (pinfunction "PA5_15") (pintype "unspecified"))
    )
    (net (code "63") (name "SWDCLK") (class "Default")
      (node (ref "H2") (pin "2") (pinfunction "2_2") (pintype "unspecified"))
      (node (ref "U2") (pin "37") (pinfunction "PA14_37") (pintype "unspecified"))
    )
    (net (code "64") (name "SWDIO") (class "Default")
      (node (ref "H2") (pin "3") (pinfunction "3_3") (pintype "unspecified"))
      (node (ref "U2") (pin "34") (pinfunction "PA13_34") (pintype "unspecified"))
    )
    (net (code "65") (name "VBAT") (class "Default")
      (node (ref "U2") (pin "1") (pinfunction "VBAT_1") (pintype "unspecified"))
    )
    (net (code "66") (name "VBAT+") (class "Default")
      (node (ref "C10") (pin "2") (pinfunction "2_2") (pintype "unspecified"))
      (node (ref "C13") (pin "1") (pinfunction "1_1") (pintype "input"))
      (node (ref "C15") (pin "2") (pinfunction "2_2") (pintype "unspecified"))
      (node (ref "C17") (pin "1") (pinfunction "1_1") (pintype "input"))
      (node (ref "C18") (pin "2") (pinfunction "2_2") (pintype "unspecified"))
      (node (ref "C19") (pin "1") (pinfunction "1_1") (pintype "input"))
      (node (ref "C20") (pin "2") (pinfunction "2_2") (pintype "unspecified"))
      (node (ref "C9") (pin "1") (pinfunction "1_1") (pintype "input"))
      (node (ref "R20") (pin "2") (pinfunction "2_2") (pintype "input"))
      (node (ref "SW3") (pin "2") (pinfunction "2_2") (pintype "input"))
      (node (ref "U6") (pin "3") (pinfunction "VIN_3") (pintype "unspecified"))
      (node (ref "U7") (pin "3") (pinfunction "VIN_3") (pintype "input"))
      (node (ref "U8") (pin "13") (pinfunction "VM2_13") (pintype "unspecified"))
      (node (ref "U8") (pin "14") (pinfunction "VM3_14") (pintype "unspecified"))
      (node (ref "U8") (pin "24") (pinfunction "VM1_24") (pintype "unspecified"))
      (node (ref "U9") (pin "13") (pinfunction "VM2_13") (pintype "unspecified"))
      (node (ref "U9") (pin "14") (pinfunction "VM3_14") (pintype "unspecified"))
      (node (ref "U9") (pin "24") (pinfunction "VM1_24") (pintype "unspecified"))
    )
    (net (code "67") (name "VCC") (class "Default")
      (node (ref "C11") (pin "2") (pinfunction "2_2") (pintype "unspecified"))
      (node (ref "C12") (pin "1") (pinfunction "1_1") (pintype "input"))
      (node (ref "C3") (pin "2") (pinfunction "2_2") (pintype "unspecified"))
      (node (ref "H12") (pin "2") (pinfunction "2_2") (pintype "input"))
      (node (ref "H14") (pin "2") (pinfunction "2_2") (pintype "input"))
      (node (ref "H2") (pin "1") (pinfunction "1_1") (pintype "unspecified"))
      (node (ref "R22") (pin "2") (pinfunction "2_2") (pintype "input"))
      (node (ref "R6") (pin "2") (pinfunction "2_2") (pintype "input"))
      (node (ref "U2") (pin "24") (pinfunction "VDD_1_24") (pintype "unspecified"))
      (node (ref "U2") (pin "36") (pinfunction "VDD_2_36") (pintype "unspecified"))
      (node (ref "U2") (pin "48") (pinfunction "VDD_3_48") (pintype "unspecified"))
      (node (ref "U2") (pin "9") (pinfunction "VDDA_9") (pintype "unspecified"))
      (node (ref "U6") (pin "2") (pinfunction "VOUT_2") (pintype "unspecified"))
      (node (ref "U8") (pin "19") (pinfunction "STBY_19") (pintype "unspecified"))
      (node (ref "U8") (pin "20") (pinfunction "VCC_20") (pintype "unspecified"))
      (node (ref "U9") (pin "19") (pinfunction "STBY_19") (pintype "unspecified"))
      (node (ref "U9") (pin "20") (pinfunction "VCC_20") (pintype "unspecified"))
    )
    (net (code "68") (name "unconnected-(SW3-Pad3)") (class "Default")
      (node (ref "SW3") (pin "3") (pinfunction "3_3") (pintype "input"))
    )
    (net (code "69") (name "unconnected-(U6-VOUT-Pad4)") (class "Default")
      (node (ref "U6") (pin "4") (pinfunction "VOUT_4") (pintype "unspecified+no_connect"))
    )
    (net (code "70") (name "unconnected-(U7-VOUT-Pad4)") (class "Default")
      (node (ref "U7") (pin "4") (pinfunction "VOUT_4") (pintype "input+no_connect"))
    )
  )
)
